# jlinker.net
KiCad netlist of a schematic drawn in Altium Designer
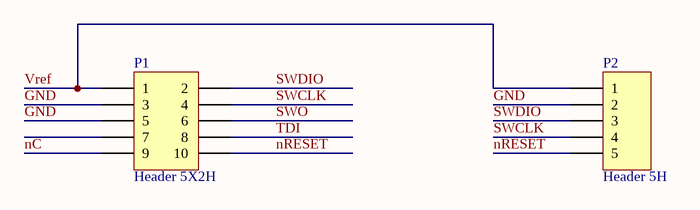
[diagram p0: jlinker.SchDoc]

(export (version "E")
  (design (tool "Eeschema 10.0.6"))
  (components
    (comp (ref "P1")
      (value "Header 5X2H")
      (footprint "MHDR2X5")
      (description "Header, 5-Pin, Dual row, Right Angle")
      (fields (field (name "PUBLISHER") "Altium Limited"))
      (libsource (lib "Miscellaneous Connectors") (part "Header 5X2H"))
    )
    (comp (ref "P2")
      (value "Header 5H")
      (footprint "HDR1X5")
      (description "Header, 5-Pin, Right Angle")
      (fields (field (name "PUBLISHER") "Altium Limited"))
      (libsource (lib "Miscellaneous Connectors") (part "Header 5H"))
    )
  )
  (nets
    (net (code "1") (name "/GND") (class "Default")
      (node (ref "P1") (pin "3") (pinfunction "3_3") (pintype "passive"))
      (node (ref "P1") (pin "5") (pinfunction "5_5") (pintype "passive"))
      (node (ref "P2") (pin "2") (pinfunction "2_2") (pintype "passive"))
    )
    (net (code "2") (name "/SWCLK") (class "Default")
      (node (ref "P1") (pin "4") (pinfunction "4_4") (pintype "passive"))
      (node (ref "P2") (pin "4") (pinfunction "4_4") (pintype "passive"))
    )
    (net (code "3") (name "/SWDIO") (class "Default")
      (node (ref "P1") (pin "2") (pinfunction "2_2") (pintype "passive"))
      (node (ref "P2") (pin "3") (pinfunction "3_3") (pintype "passive"))
    )
    (net (code "4") (name "/SWO") (class "Default")
      (node (ref "P1") (pin "6") (pinfunction "6_6") (pintype "passive"))
    )
    (net (code "5") (name "/TDI") (class "Default")
      (node (ref "P1") (pin "8") (pinfunction "8_8") (pintype "passive"))
    )
    (net (code "6") (name "/Vref") (class "Default")
      (node (ref "P1") (pin "1") (pinfunction "1_1") (pintype "passive"))
      (node (ref "P2") (pin "1") (pinfunction "1_1") (pintype "passive"))
    )
    (net (code "7") (name "/nC") (class "Default")
      (node (ref "P1") (pin "9") (pinfunction "9_9") (pintype "passive"))
    )
    (net (code "8") (name "/nRESET") (class "Default")
      (node (ref "P1") (pin "10") (pinfunction "10_10") (pintype "passive"))
      (node (ref "P2") (pin "5") (pinfunction "5_5") (pintype "passive"))
    )
    (net (code "9") (name "unconnected-(P1-Pad7)") (class "Default")
      (node (ref "P1") (pin "7") (pinfunction "7_7") (pintype "passive"))
    )
  )
)
